# untitled.net
KiCad netlist of a schematic drawn in EAGLE
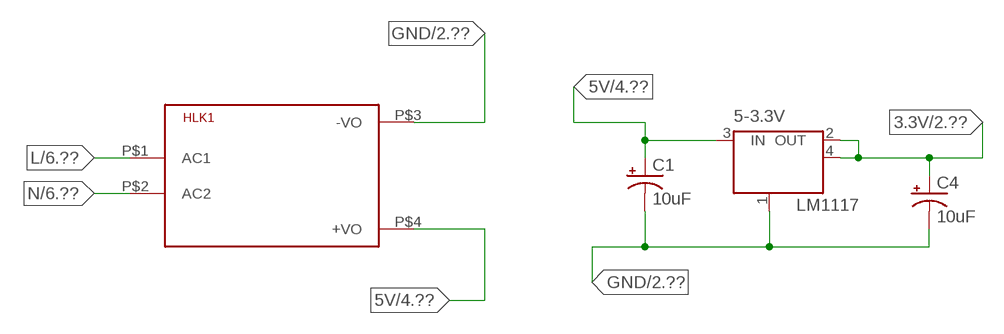
[diagram p0: schematic, sheet 1]
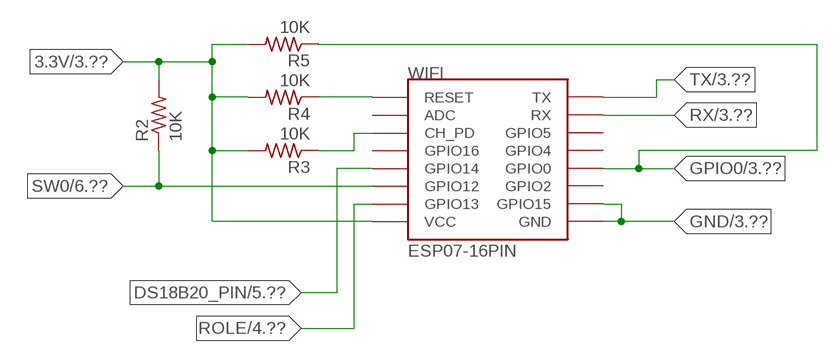
[diagram p1: schematic, sheet 2]
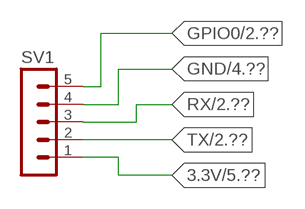
[diagram p2: schematic, sheet 3]
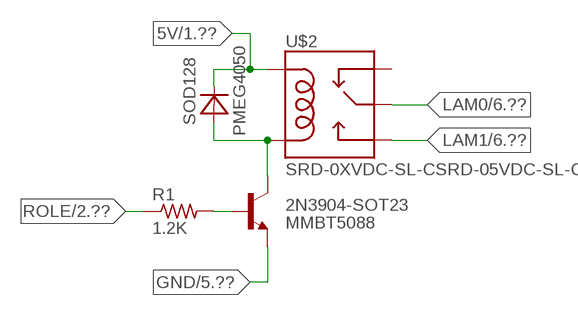
[diagram p3: schematic, sheet 4]
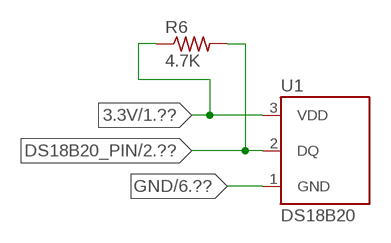
[diagram p4: schematic, sheet 5]
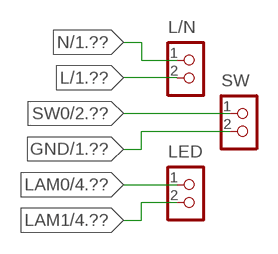
[diagram p5: schematic, sheet 6]

(export (version "E")
  (design (tool "Eeschema 10.0.6"))
  (components
    (comp (ref "SV1")
      (value "MA05-1")
      (footprint "eagle-import:MA05-1")
      (libsource (lib "eagle-import") (part "MA05-1"))
    )
    (comp (ref "5-3.3V")
      (value "LM1117")
      (footprint "eagle-import:SOT223")
      (libsource (lib "eagle-import") (part "LM1117"))
    )
    (comp (ref "C1")
      (value "10uF")
      (footprint "eagle-import:EIA3216")
      (libsource (lib "eagle-import") (part "10UF-TANT"))
    )
    (comp (ref "C4")
      (value "10uF")
      (footprint "eagle-import:EIA3216")
      (libsource (lib "eagle-import") (part "10UF-TANT"))
    )
    (comp (ref "HLK1")
      (value "HLK-PM013W")
      (footprint "eagle-import:HLK-PM01")
      (libsource (lib "eagle-import") (part "HLK-PM013W"))
    )
    (comp (ref "L/N")
      (value "CON_TERMINAL_BLOCK_02-5MM")
      (footprint "eagle-import:TERMINAL_BLOCK_2P_5")
      (libsource (lib "eagle-import") (part "CON_TERMINAL_BLOCK_02-5MM"))
    )
    (comp (ref "LED")
      (value "CON_TERMINAL_BLOCK_02-5MM")
      (footprint "eagle-import:TERMINAL_BLOCK_2P_5")
      (libsource (lib "eagle-import") (part "CON_TERMINAL_BLOCK_02-5MM"))
    )
    (comp (ref "SW")
      (value "CON_TERMINAL_BLOCK_02-5MM")
      (footprint "eagle-import:TERMINAL_BLOCK_2P_5")
      (libsource (lib "eagle-import") (part "CON_TERMINAL_BLOCK_02-5MM"))
    )
    (comp (ref "R6")
      (value "4.7K")
      (footprint "eagle-import:R0805")
      (libsource (lib "eagle-import") (part "R-US_R0805"))
    )
    (comp (ref "U1")
      (value "DS18B20")
      (footprint "eagle-import:TO-92-AMMO")
      (libsource (lib "eagle-import") (part "DS18B20"))
    )
    (comp (ref "2N3904-SOT23")
      (value "MMBT5088")
      (footprint "eagle-import:SOT23-3")
      (libsource (lib "eagle-import") (part "TRANSISTOR_NPNMMBT5088"))
    )
    (comp (ref "R1")
      (value "1.2K")
      (footprint "eagle-import:R0805")
      (libsource (lib "eagle-import") (part "R-US_R0805"))
    )
    (comp (ref "SOD128")
      (value "PMEG4050")
      (footprint "eagle-import:SOD128")
      (libsource (lib "eagle-import") (part "PMEG4050"))
    )
    (comp (ref "U$2")
      (value "SRD-0XVDC-SL-CSRD-05VDC-SL-C")
      (footprint "eagle-import:SRD-0XVDC-SL-C")
      (libsource (lib "eagle-import") (part "SRD-0XVDC-SL-CSRD-05VDC-SL-C"))
    )
    (comp (ref "R2")
      (value "10K")
      (footprint "eagle-import:R0805")
      (libsource (lib "eagle-import") (part "R-US_R0805"))
    )
    (comp (ref "R3")
      (value "10K")
      (footprint "eagle-import:R0805")
      (libsource (lib "eagle-import") (part "R-US_R0805"))
    )
    (comp (ref "R4")
      (value "10K")
      (footprint "eagle-import:R0805")
      (libsource (lib "eagle-import") (part "R-US_R0805"))
    )
    (comp (ref "R5")
      (value "10K")
      (footprint "eagle-import:R0805")
      (libsource (lib "eagle-import") (part "R-US_R0805"))
    )
    (comp (ref "WIFI")
      (value "ESP07-16PIN")
      (footprint "eagle-import:ESP07-16PIN")
      (libsource (lib "eagle-import") (part "ESP07-16PIN"))
    )
  )
  (nets
    (net (code "1") (name "3.3V") (class "Default")
      (node (ref "5-3.3V") (pin "2") (pinfunction "OUT_2") (pintype "passive"))
      (node (ref "5-3.3V") (pin "4") (pinfunction "OUT_4") (pintype "passive"))
      (node (ref "C4") (pin "A") (pinfunction "+_A") (pintype "passive"))
      (node (ref "R2") (pin "2") (pinfunction "2_2") (pintype "passive"))
      (node (ref "R3") (pin "2") (pinfunction "2_2") (pintype "passive"))
      (node (ref "R4") (pin "2") (pinfunction "2_2") (pintype "passive"))
      (node (ref "R5") (pin "2") (pinfunction "2_2") (pintype "passive"))
      (node (ref "R6") (pin "1") (pinfunction "1_1") (pintype "passive"))
      (node (ref "SV1") (pin "1") (pinfunction "1_1") (pintype "passive"))
      (node (ref "U1") (pin "3") (pinfunction "VDD_3") (pintype "power_in"))
      (node (ref "WIFI") (pin "VCC") (pinfunction "VCC_VCC") (pintype "bidirectional"))
    )
    (net (code "2") (name "5V") (class "Default")
      (node (ref "5-3.3V") (pin "3") (pinfunction "IN_3") (pintype "input"))
      (node (ref "C1") (pin "A") (pinfunction "+_A") (pintype "passive"))
      (node (ref "HLK1") (pin "P$4") (pinfunction "+VO_P$4") (pintype "bidirectional"))
      (node (ref "SOD128") (pin "1") (pinfunction "C_1") (pintype "passive"))
      (node (ref "U$2") (pin "COIL1") (pinfunction "COIL1_COIL1") (pintype "bidirectional"))
    )
    (net (code "3") (name "DS18B20_PIN") (class "Default")
      (node (ref "R6") (pin "2") (pinfunction "2_2") (pintype "passive"))
      (node (ref "U1") (pin "2") (pinfunction "DQ_2") (pintype "bidirectional"))
      (node (ref "WIFI") (pin "GPIO14") (pinfunction "GPIO14_GPIO14") (pintype "bidirectional"))
    )
    (net (code "4") (name "GND") (class "Default")
      (node (ref "2N3904-SOT23") (pin "2") (pinfunction "E_2") (pintype "passive"))
      (node (ref "5-3.3V") (pin "1") (pinfunction "GND/ADJ_1") (pintype "input"))
      (node (ref "C1") (pin "C") (pinfunction "-_C") (pintype "passive"))
      (node (ref "C4") (pin "C") (pinfunction "-_C") (pintype "passive"))
      (node (ref "HLK1") (pin "P$3") (pinfunction "-VO_P$3") (pintype "bidirectional"))
      (node (ref "SV1") (pin "4") (pinfunction "4_4") (pintype "passive"))
      (node (ref "SW") (pin "2") (pinfunction "2_2") (pintype "passive"))
      (node (ref "U1") (pin "1") (pinfunction "GND_1") (pintype "power_in"))
      (node (ref "WIFI") (pin "GND") (pinfunction "GND_GND") (pintype "bidirectional"))
      (node (ref "WIFI") (pin "GPIO15") (pinfunction "GPIO15_GPIO15") (pintype "bidirectional"))
    )
    (net (code "5") (name "GPIO0") (class "Default")
      (node (ref "R5") (pin "1") (pinfunction "1_1") (pintype "passive"))
      (node (ref "SV1") (pin "5") (pinfunction "5_5") (pintype "passive"))
      (node (ref "WIFI") (pin "GPIO0") (pinfunction "GPIO0_GPIO0") (pintype "bidirectional"))
    )
    (net (code "6") (name "L") (class "Default")
      (node (ref "HLK1") (pin "P$1") (pinfunction "AC1_P$1") (pintype "bidirectional"))
      (node (ref "L/N") (pin "2") (pinfunction "2_2") (pintype "passive"))
    )
    (net (code "7") (name "LAM0") (class "Default")
      (node (ref "LED") (pin "1") (pinfunction "1_1") (pintype "passive"))
      (node (ref "U$2") (pin "SWCOMMON") (pinfunction "SWCOMMON_SWCOMMON") (pintype "bidirectional"))
    )
    (net (code "8") (name "LAM1") (class "Default")
      (node (ref "LED") (pin "2") (pinfunction "2_2") (pintype "passive"))
      (node (ref "U$2") (pin "SWOPEN") (pinfunction "SWOPEN_SWOPEN") (pintype "bidirectional"))
    )
    (net (code "9") (name "N") (class "Default")
      (node (ref "HLK1") (pin "P$2") (pinfunction "AC2_P$2") (pintype "bidirectional"))
      (node (ref "L/N") (pin "1") (pinfunction "1_1") (pintype "passive"))
    )
    (net (code "10") (name "Net-(2N3904-SOT23-B)") (class "Default")
      (node (ref "2N3904-SOT23") (pin "1") (pinfunction "B_1") (pintype "passive"))
      (node (ref "R1") (pin "2") (pinfunction "2_2") (pintype "passive"))
    )
    (net (code "11") (name "Net-(2N3904-SOT23-C)") (class "Default")
      (node (ref "2N3904-SOT23") (pin "3") (pinfunction "C_3") (pintype "passive"))
      (node (ref "SOD128") (pin "2") (pinfunction "A_2") (pintype "passive"))
      (node (ref "U$2") (pin "COIL0") (pinfunction "COIL0_COIL0") (pintype "bidirectional"))
    )
    (net (code "12") (name "Net-(R3-Pad1)") (class "Default")
      (node (ref "R3") (pin "1") (pinfunction "1_1") (pintype "passive"))
      (node (ref "WIFI") (pin "CH_PD") (pinfunction "CH_PD_CH_PD") (pintype "bidirectional"))
    )
    (net (code "13") (name "Net-(WIFI-RESET)") (class "Default")
      (node (ref "R4") (pin "1") (pinfunction "1_1") (pintype "passive"))
      (node (ref "WIFI") (pin "REST") (pinfunction "RESET_REST") (pintype "bidirectional"))
    )
    (net (code "14") (name "ROLE") (class "Default")
      (node (ref "R1") (pin "1") (pinfunction "1_1") (pintype "passive"))
      (node (ref "WIFI") (pin "GPIO13") (pinfunction "GPIO13_GPIO13") (pintype "bidirectional"))
    )
    (net (code "15") (name "RX") (class "Default")
      (node (ref "SV1") (pin "3") (pinfunction "3_3") (pintype "passive"))
      (node (ref "WIFI") (pin "RX") (pinfunction "RX_RX") (pintype "bidirectional"))
    )
    (net (code "16") (name "SW0") (class "Default")
      (node (ref "R2") (pin "1") (pinfunction "1_1") (pintype "passive"))
      (node (ref "SW") (pin "1") (pinfunction "1_1") (pintype "passive"))
      (node (ref "WIFI") (pin "GPIO12") (pinfunction "GPIO12_GPIO12") (pintype "bidirectional"))
    )
    (net (code "17") (name "TX") (class "Default")
      (node (ref "SV1") (pin "2") (pinfunction "2_2") (pintype "passive"))
      (node (ref "WIFI") (pin "TX") (pinfunction "TX_TX") (pintype "bidirectional"))
    )
    (net (code "18") (name "unconnected-(U$2-SWCLOSE-PadSWCLOSED)") (class "Default")
      (node (ref "U$2") (pin "SWCLOSED") (pinfunction "SWCLOSE_SWCLOSED") (pintype "bidirectional"))
    )
    (net (code "19") (name "unconnected-(WIFI-PadADC)") (class "Default")
      (node (ref "WIFI") (pin "ADC") (pinfunction "ADC_ADC") (pintype "bidirectional"))
    )
    (net (code "20") (name "unconnected-(WIFI-PadGPIO2)") (class "Default")
      (node (ref "WIFI") (pin "GPIO2") (pinfunction "GPIO2_GPIO2") (pintype "bidirectional"))
    )
    (net (code "21") (name "unconnected-(WIFI-PadGPIO4)") (class "Default")
      (node (ref "WIFI") (pin "GPIO4") (pinfunction "GPIO4_GPIO4") (pintype "bidirectional"))
    )
    (net (code "22") (name "unconnected-(WIFI-PadGPIO5)") (class "Default")
      (node (ref "WIFI") (pin "GPIO5") (pinfunction "GPIO5_GPIO5") (pintype "bidirectional"))
    )
    (net (code "23") (name "unconnected-(WIFI-PadGPIO16)") (class "Default")
      (node (ref "WIFI") (pin "GPIO16") (pinfunction "GPIO16_GPIO16") (pintype "bidirectional"))
    )
  )
)
